# mcu.net
KiCad netlist of a schematic drawn in Altium Designer
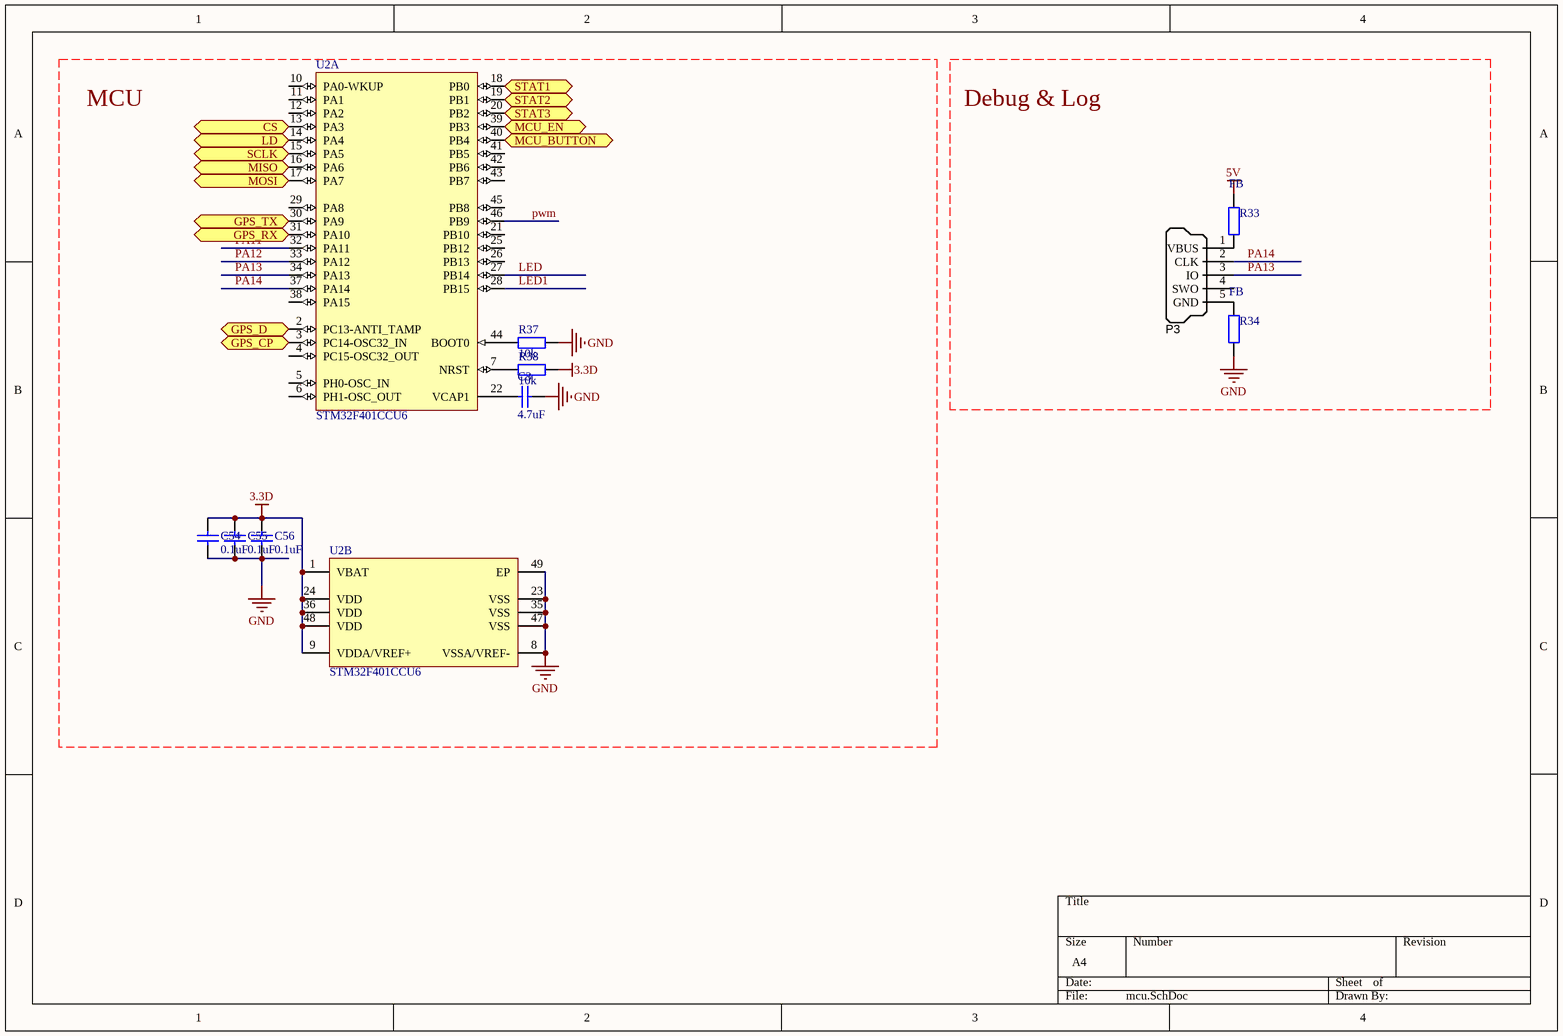
[diagram p0: mcu.SchDoc]

(export (version "E")
  (design (tool "Eeschema 10.0.6"))
  (components
    (comp (ref "C3")
      (value "4.7uF")
      (footprint "0603")
      (description "Capacitor")
      (fields (field (name "Comment") "Cap") (field (name "PUBLISHER") "Altium Limited"))
      (libsource (lib "RTC6705") (part "Cap"))
    )
    (comp (ref "C54")
      (value "0.1uF")
      (footprint "0402")
      (description "Capacitor")
      (fields (field (name "Comment") "Cap") (field (name "PUBLISHER") "Altium Limited"))
      (libsource (lib "RTC6705") (part "Cap"))
    )
    (comp (ref "C55")
      (value "0.1uF")
      (footprint "0402")
      (description "Capacitor")
      (fields (field (name "Comment") "Cap") (field (name "PUBLISHER") "Altium Limited"))
      (libsource (lib "RTC6705") (part "Cap"))
    )
    (comp (ref "C56")
      (value "0.1uF")
      (footprint "0402")
      (description "Capacitor")
      (fields (field (name "Comment") "Cap") (field (name "PUBLISHER") "Altium Limited"))
      (libsource (lib "RTC6705") (part "Cap"))
    )
    (comp (ref "P3")
      (value "SWD_MicroUSB")
      (footprint "MICRO-YZX")
      (description "Connector SMD USB Micro Type B middle mount")
      (libsource (lib "sch") (part "SWD_MicroUSB"))
    )
    (comp (ref "R33")
      (value "FB")
      (footprint "0603L")
      (description "Resistor")
      (fields (field (name "PUBLISHER") "Altium Limited"))
      (libsource (lib "") (part "Res2_1"))
    )
    (comp (ref "R34")
      (value "FB")
      (footprint "0603L")
      (description "Resistor")
      (fields (field (name "PUBLISHER") "Altium Limited"))
      (libsource (lib "") (part "Res2_1"))
    )
    (comp (ref "R37")
      (value "10k")
      (footprint "0402")
      (description "Resistor")
      (fields (field (name "Comment") "Res2") (field (name "PUBLISHER") "Altium Limited"))
      (libsource (lib "RTC6705") (part "Res2"))
    )
    (comp (ref "R38")
      (value "10k")
      (footprint "0402")
      (description "Resistor")
      (fields (field (name "Comment") "Res2") (field (name "PUBLISHER") "Altium Limited"))
      (libsource (lib "") (part "Res2_2"))
    )
    (comp (ref "U2")
      (value "STM32F401CCU6")
      (footprint "STM-UFQFPN48_N")
      (fields (field (name "MANUFACTURER") "STMicroelectronics"))
      (libsource (lib "STMicroelectronics STM32 F4") (part "STM32F401CCU6"))
    )
  )
  (nets
    (net (code "1") (name "/CS") (class "Default")
      (node (ref "U2") (pin "13") (pinfunction "PA3_13") (pintype "bidirectional"))
    )
    (net (code "2") (name "/GPS_CP") (class "Default")
      (node (ref "U2") (pin "3") (pinfunction "PC14-OSC32_IN_3") (pintype "bidirectional"))
    )
    (net (code "3") (name "/GPS_D") (class "Default")
      (node (ref "U2") (pin "2") (pinfunction "PC13-ANTI_TAMP_2") (pintype "bidirectional"))
    )
    (net (code "4") (name "/GPS_RX") (class "Default")
      (node (ref "U2") (pin "31") (pinfunction "PA10_31") (pintype "bidirectional"))
    )
    (net (code "5") (name "/GPS_TX") (class "Default")
      (node (ref "U2") (pin "30") (pinfunction "PA9_30") (pintype "bidirectional"))
    )
    (net (code "6") (name "/LD") (class "Default")
      (node (ref "U2") (pin "14") (pinfunction "PA4_14") (pintype "bidirectional"))
    )
    (net (code "7") (name "/LED") (class "Default")
      (node (ref "U2") (pin "27") (pinfunction "PB14_27") (pintype "bidirectional"))
    )
    (net (code "8") (name "/LED1") (class "Default")
      (node (ref "U2") (pin "28") (pinfunction "PB15_28") (pintype "bidirectional"))
    )
    (net (code "9") (name "/MCU_BUTTON") (class "Default")
      (node (ref "U2") (pin "40") (pinfunction "PB4_40") (pintype "bidirectional"))
    )
    (net (code "10") (name "/MCU_EN") (class "Default")
      (node (ref "U2") (pin "39") (pinfunction "PB3_39") (pintype "bidirectional"))
    )
    (net (code "11") (name "/MISO") (class "Default")
      (node (ref "U2") (pin "16") (pinfunction "PA6_16") (pintype "bidirectional"))
    )
    (net (code "12") (name "/MOSI") (class "Default")
      (node (ref "U2") (pin "17") (pinfunction "PA7_17") (pintype "bidirectional"))
    )
    (net (code "13") (name "/PA11") (class "Default")
      (node (ref "U2") (pin "32") (pinfunction "PA11_32") (pintype "bidirectional"))
    )
    (net (code "14") (name "/PA12") (class "Default")
      (node (ref "U2") (pin "33") (pinfunction "PA12_33") (pintype "bidirectional"))
    )
    (net (code "15") (name "/PA13") (class "Default")
      (node (ref "P3") (pin "3") (pinfunction "IO_3") (pintype "passive"))
      (node (ref "U2") (pin "34") (pinfunction "PA13_34") (pintype "bidirectional"))
    )
    (net (code "16") (name "/PA14") (class "Default")
      (node (ref "P3") (pin "2") (pinfunction "CLK_2") (pintype "passive"))
      (node (ref "U2") (pin "37") (pinfunction "PA14_37") (pintype "bidirectional"))
    )
    (net (code "17") (name "/SCLK") (class "Default")
      (node (ref "U2") (pin "15") (pinfunction "PA5_15") (pintype "bidirectional"))
    )
    (net (code "18") (name "/STAT1") (class "Default")
      (node (ref "U2") (pin "18") (pinfunction "PB0_18") (pintype "bidirectional"))
    )
    (net (code "19") (name "/STAT2") (class "Default")
      (node (ref "U2") (pin "19") (pinfunction "PB1_19") (pintype "bidirectional"))
    )
    (net (code "20") (name "/STAT3") (class "Default")
      (node (ref "U2") (pin "20") (pinfunction "PB2_20") (pintype "bidirectional"))
    )
    (net (code "21") (name "/pwm") (class "Default")
      (node (ref "U2") (pin "46") (pinfunction "PB9_46") (pintype "bidirectional"))
    )
    (net (code "22") (name "3.3D") (class "Default")
      (node (ref "C54") (pin "2") (pinfunction "2_2") (pintype "passive"))
      (node (ref "C55") (pin "2") (pinfunction "2_2") (pintype "passive"))
      (node (ref "C56") (pin "2") (pinfunction "2_2") (pintype "passive"))
      (node (ref "R38") (pin "1") (pinfunction "1_1") (pintype "passive"))
      (node (ref "U2") (pin "1") (pinfunction "VBAT_1") (pintype "power_in"))
      (node (ref "U2") (pin "24") (pinfunction "VDD_24") (pintype "power_in"))
      (node (ref "U2") (pin "36") (pinfunction "VDD_36") (pintype "power_in"))
      (node (ref "U2") (pin "48") (pinfunction "VDD_48") (pintype "power_in"))
      (node (ref "U2") (pin "9") (pinfunction "VDDA/VREF+_9") (pintype "power_in"))
    )
    (net (code "23") (name "5V") (class "Default")
      (node (ref "R33") (pin "2") (pinfunction "2_2") (pintype "passive"))
    )
    (net (code "24") (name "GND") (class "Default")
      (node (ref "C3") (pin "1") (pinfunction "1_1") (pintype "passive"))
      (node (ref "C54") (pin "1") (pinfunction "1_1") (pintype "passive"))
      (node (ref "C55") (pin "1") (pinfunction "1_1") (pintype "passive"))
      (node (ref "C56") (pin "1") (pinfunction "1_1") (pintype "passive"))
      (node (ref "R34") (pin "1") (pinfunction "1_1") (pintype "passive"))
      (node (ref "R37") (pin "2") (pinfunction "2_2") (pintype "passive"))
      (node (ref "U2") (pin "23") (pinfunction "VSS_23") (pintype "power_in"))
      (node (ref "U2") (pin "35") (pinfunction "VSS_35") (pintype "power_in"))
      (node (ref "U2") (pin "47") (pinfunction "VSS_47") (pintype "power_in"))
      (node (ref "U2") (pin "49") (pinfunction "EP_49") (pintype "power_in"))
      (node (ref "U2") (pin "8") (pinfunction "VSSA/VREF-_8") (pintype "power_in"))
    )
    (net (code "25") (name "Net-(P3-GND)") (class "Default")
      (node (ref "P3") (pin "5") (pinfunction "GND_5") (pintype "passive"))
      (node (ref "R34") (pin "2") (pinfunction "2_2") (pintype "passive"))
    )
    (net (code "26") (name "Net-(P3-VBUS)") (class "Default")
      (node (ref "P3") (pin "1") (pinfunction "VBUS_1") (pintype "passive"))
      (node (ref "R33") (pin "1") (pinfunction "1_1") (pintype "passive"))
    )
    (net (code "27") (name "Net-(U2A-BOOT0)") (class "Default")
      (node (ref "R37") (pin "1") (pinfunction "1_1") (pintype "passive"))
      (node (ref "U2") (pin "44") (pinfunction "BOOT0_44") (pintype "input"))
    )
    (net (code "28") (name "Net-(U2A-NRST)") (class "Default")
      (node (ref "R38") (pin "2") (pinfunction "2_2") (pintype "passive"))
      (node (ref "U2") (pin "7") (pinfunction "NRST_7") (pintype "bidirectional"))
    )
    (net (code "29") (name "Net-(U2A-VCAP1)") (class "Default")
      (node (ref "C3") (pin "2") (pinfunction "2_2") (pintype "passive"))
      (node (ref "U2") (pin "22") (pinfunction "VCAP1_22") (pintype "power_in"))
    )
    (net (code "30") (name "unconnected-(P3-SWO-Pad4)") (class "Default")
      (node (ref "P3") (pin "4") (pinfunction "SWO_4") (pintype "passive"))
    )
    (net (code "31") (name "unconnected-(U2A-PA0-WKUP-Pad10)") (class "Default")
      (node (ref "U2") (pin "10") (pinfunction "PA0-WKUP_10") (pintype "bidirectional"))
    )
    (net (code "32") (name "unconnected-(U2A-PA1-Pad11)") (class "Default")
      (node (ref "U2") (pin "11") (pinfunction "PA1_11") (pintype "bidirectional"))
    )
    (net (code "33") (name "unconnected-(U2A-PA2-Pad12)") (class "Default")
      (node (ref "U2") (pin "12") (pinfunction "PA2_12") (pintype "bidirectional"))
    )
    (net (code "34") (name "unconnected-(U2A-PA8-Pad29)") (class "Default")
      (node (ref "U2") (pin "29") (pinfunction "PA8_29") (pintype "bidirectional"))
    )
    (net (code "35") (name "unconnected-(U2A-PA15-Pad38)") (class "Default")
      (node (ref "U2") (pin "38") (pinfunction "PA15_38") (pintype "bidirectional"))
    )
    (net (code "36") (name "unconnected-(U2A-PB5-Pad41)") (class "Default")
      (node (ref "U2") (pin "41") (pinfunction "PB5_41") (pintype "bidirectional"))
    )
    (net (code "37") (name "unconnected-(U2A-PB6-Pad42)") (class "Default")
      (node (ref "U2") (pin "42") (pinfunction "PB6_42") (pintype "bidirectional"))
    )
    (net (code "38") (name "unconnected-(U2A-PB7-Pad43)") (class "Default")
      (node (ref "U2") (pin "43") (pinfunction "PB7_43") (pintype "bidirectional"))
    )
    (net (code "39") (name "unconnected-(U2A-PB8-Pad45)") (class "Default")
      (node (ref "U2") (pin "45") (pinfunction "PB8_45") (pintype "bidirectional"))
    )
    (net (code "40") (name "unconnected-(U2A-PB10-Pad21)") (class "Default")
      (node (ref "U2") (pin "21") (pinfunction "PB10_21") (pintype "bidirectional"))
    )
    (net (code "41") (name "unconnected-(U2A-PB12-Pad25)") (class "Default")
      (node (ref "U2") (pin "25") (pinfunction "PB12_25") (pintype "bidirectional"))
    )
    (net (code "42") (name "unconnected-(U2A-PB13-Pad26)") (class "Default")
      (node (ref "U2") (pin "26") (pinfunction "PB13_26") (pintype "bidirectional"))
    )
    (net (code "43") (name "unconnected-(U2A-PC15-OSC32_OUT-Pad4)") (class "Default")
      (node (ref "U2") (pin "4") (pinfunction "PC15-OSC32_OUT_4") (pintype "bidirectional"))
    )
    (net (code "44") (name "unconnected-(U2A-PH0-OSC_IN-Pad5)") (class "Default")
      (node (ref "U2") (pin "5") (pinfunction "PH0-OSC_IN_5") (pintype "bidirectional"))
    )
    (net (code "45") (name "unconnected-(U2A-PH1-OSC_OUT-Pad6)") (class "Default")
      (node (ref "U2") (pin "6") (pinfunction "PH1-OSC_OUT_6") (pintype "bidirectional"))
    )
  )
)
